# CH340E.net
KiCad netlist of a schematic drawn in EAGLE
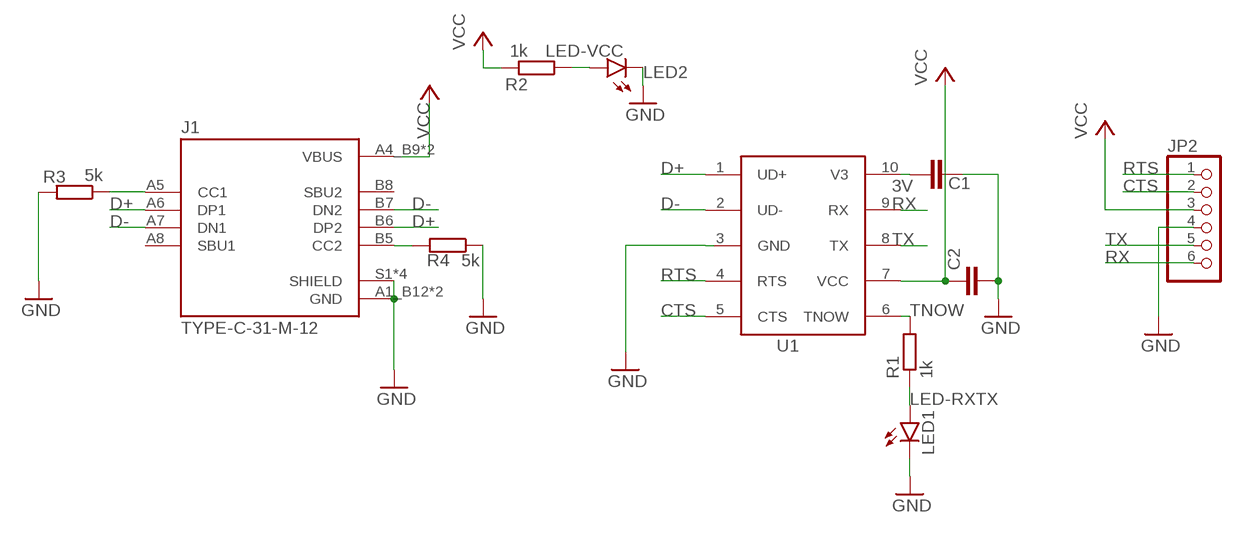
[diagram p0: schematic, sheet 1]

(export (version "E")
  (design (tool "Eeschema 10.0.6"))
  (components
    (comp (ref "C1")
      (value "C-EUC0603")
      (footprint "eagle-import:C0603")
      (libsource (lib "eagle-import") (part "C-EUC0603"))
    )
    (comp (ref "C2")
      (value "C-EUC0603")
      (footprint "eagle-import:C0603")
      (libsource (lib "eagle-import") (part "C-EUC0603"))
    )
    (comp (ref "J1")
      (value "TYPE-C-31-M-12")
      (footprint "eagle-import:HRO_TYPE-C-31-M-12")
      (fields (field (name "MF") "HRO Electronics Co., Ltd."))
      (libsource (lib "eagle-import") (part "TYPE-C-31-M-12"))
    )
    (comp (ref "JP2")
      (value "PINHD-1X6")
      (footprint "eagle-import:1X06")
      (libsource (lib "eagle-import") (part "PINHD-1X6"))
    )
    (comp (ref "LED1")
      (value "LEDCHIPLED_0603")
      (footprint "eagle-import:CHIPLED_0603")
      (libsource (lib "eagle-import") (part "LEDCHIPLED_0603"))
    )
    (comp (ref "LED2")
      (value "LEDCHIPLED_0603")
      (footprint "eagle-import:CHIPLED_0603")
      (libsource (lib "eagle-import") (part "LEDCHIPLED_0603"))
    )
    (comp (ref "R1")
      (value "1k")
      (footprint "eagle-import:R0603")
      (libsource (lib "eagle-import") (part "R-EU_R0603"))
    )
    (comp (ref "R2")
      (value "1k")
      (footprint "eagle-import:R0603")
      (libsource (lib "eagle-import") (part "R-EU_R0603"))
    )
    (comp (ref "R3")
      (value "5k")
      (footprint "eagle-import:R0603")
      (libsource (lib "eagle-import") (part "R-EU_R0603"))
    )
    (comp (ref "R4")
      (value "5k")
      (footprint "eagle-import:R0603")
      (libsource (lib "eagle-import") (part "R-EU_R0603"))
    )
    (comp (ref "U1")
      (value "CH340ESMD")
      (footprint "eagle-import:MSOP10")
      (libsource (lib "eagle-import") (part "CH340ESMD"))
    )
  )
  (nets
    (net (code "1") (name "/3V") (class "Default")
      (node (ref "C1") (pin "1") (pinfunction "1_1") (pintype "passive"))
      (node (ref "U1") (pin "10") (pinfunction "V3_10") (pintype "power_in"))
    )
    (net (code "2") (name "/CTS") (class "Default")
      (node (ref "JP2") (pin "2") (pinfunction "2_2") (pintype "passive"))
      (node (ref "U1") (pin "5") (pinfunction "CTS_5") (pintype "input"))
    )
    (net (code "3") (name "/D+") (class "Default")
      (node (ref "J1") (pin "A6") (pinfunction "DP1_A6") (pintype "bidirectional"))
      (node (ref "J1") (pin "B6") (pinfunction "DP2_B6") (pintype "bidirectional"))
      (node (ref "U1") (pin "1") (pinfunction "UD+_1") (pintype "bidirectional"))
    )
    (net (code "4") (name "/D-") (class "Default")
      (node (ref "J1") (pin "A7") (pinfunction "DN1_A7") (pintype "bidirectional"))
      (node (ref "J1") (pin "B7") (pinfunction "DN2_B7") (pintype "bidirectional"))
      (node (ref "U1") (pin "2") (pinfunction "UD-_2") (pintype "bidirectional"))
    )
    (net (code "5") (name "/LED-RXTX") (class "Default")
      (node (ref "LED1") (pin "A") (pinfunction "A_A") (pintype "passive"))
      (node (ref "R1") (pin "1") (pinfunction "1_1") (pintype "passive"))
    )
    (net (code "6") (name "/LED-VCC") (class "Default")
      (node (ref "LED2") (pin "A") (pinfunction "A_A") (pintype "passive"))
      (node (ref "R2") (pin "1") (pinfunction "1_1") (pintype "passive"))
    )
    (net (code "7") (name "/RTS") (class "Default")
      (node (ref "JP2") (pin "1") (pinfunction "1_1") (pintype "passive"))
      (node (ref "U1") (pin "4") (pinfunction "RTS_4") (pintype "output"))
    )
    (net (code "8") (name "/RX") (class "Default")
      (node (ref "JP2") (pin "6") (pinfunction "6_6") (pintype "passive"))
      (node (ref "U1") (pin "9") (pinfunction "RX_9") (pintype "input"))
    )
    (net (code "9") (name "/TNOW") (class "Default")
      (node (ref "R1") (pin "2") (pinfunction "2_2") (pintype "passive"))
      (node (ref "U1") (pin "6") (pinfunction "TNOW_6") (pintype "output"))
    )
    (net (code "10") (name "/TX") (class "Default")
      (node (ref "JP2") (pin "5") (pinfunction "5_5") (pintype "passive"))
      (node (ref "U1") (pin "8") (pinfunction "TX_8") (pintype "output"))
    )
    (net (code "11") (name "GND") (class "Default")
      (node (ref "C1") (pin "2") (pinfunction "2_2") (pintype "passive"))
      (node (ref "C2") (pin "2") (pinfunction "2_2") (pintype "passive"))
      (node (ref "J1") (pin "A1_B12") (pinfunction "GND_A1_B12") (pintype "power_in"))
      (node (ref "J1") (pin "B1_A12") (pinfunction "GND_B1_A12") (pintype "power_in"))
      (node (ref "J1") (pin "S1") (pinfunction "SHIELD_S1") (pintype "passive"))
      (node (ref "J1") (pin "S2") (pinfunction "SHIELD_S2") (pintype "passive"))
      (node (ref "J1") (pin "S3") (pinfunction "SHIELD_S3") (pintype "passive"))
      (node (ref "J1") (pin "S4") (pinfunction "SHIELD_S4") (pintype "passive"))
      (node (ref "JP2") (pin "4") (pinfunction "4_4") (pintype "passive"))
      (node (ref "LED1") (pin "C") (pinfunction "C_C") (pintype "passive"))
      (node (ref "LED2") (pin "C") (pinfunction "C_C") (pintype "passive"))
      (node (ref "R3") (pin "2") (pinfunction "2_2") (pintype "passive"))
      (node (ref "R4") (pin "1") (pinfunction "1_1") (pintype "passive"))
      (node (ref "U1") (pin "3") (pinfunction "GND_3") (pintype "power_in"))
    )
    (net (code "12") (name "Net-(J1-CC1)") (class "Default")
      (node (ref "J1") (pin "A5") (pinfunction "CC1_A5") (pintype "bidirectional"))
      (node (ref "R3") (pin "1") (pinfunction "1_1") (pintype "passive"))
    )
    (net (code "13") (name "Net-(J1-CC2)") (class "Default")
      (node (ref "J1") (pin "B5") (pinfunction "CC2_B5") (pintype "bidirectional"))
      (node (ref "R4") (pin "2") (pinfunction "2_2") (pintype "passive"))
    )
    (net (code "14") (name "VCC") (class "Default")
      (node (ref "C2") (pin "1") (pinfunction "1_1") (pintype "passive"))
      (node (ref "J1") (pin "A4_B9") (pinfunction "VBUS_A4_B9") (pintype "power_in"))
      (node (ref "J1") (pin "B4_A9") (pinfunction "VBUS_B4_A9") (pintype "power_in"))
      (node (ref "JP2") (pin "3") (pinfunction "3_3") (pintype "passive"))
      (node (ref "R2") (pin "2") (pinfunction "2_2") (pintype "passive"))
      (node (ref "U1") (pin "7") (pinfunction "VCC_7") (pintype "power_in"))
    )
    (net (code "15") (name "unconnected-(J1-SBU1-PadA8)") (class "Default")
      (node (ref "J1") (pin "A8") (pinfunction "SBU1_A8") (pintype "bidirectional"))
    )
    (net (code "16") (name "unconnected-(J1-SBU2-PadB8)") (class "Default")
      (node (ref "J1") (pin "B8") (pinfunction "SBU2_B8") (pintype "bidirectional"))
    )
  )
)
